# OBCI32_RN42.net
KiCad netlist of a schematic drawn in EAGLE
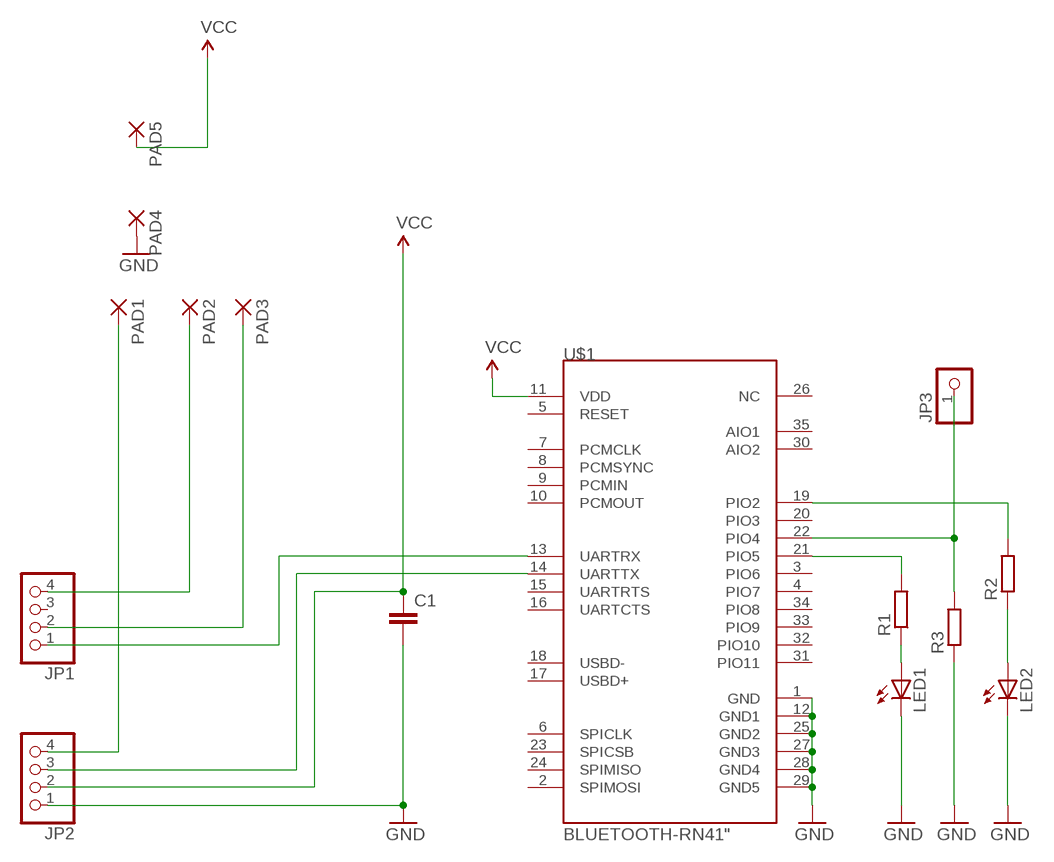
[diagram p0: schematic, sheet 1]

(export (version "E")
  (design (tool "Eeschema 10.0.6"))
  (components
    (comp (ref "C1")
      (value "C-EUC0805")
      (footprint "eagle-import:C0805")
      (libsource (lib "eagle-import") (part "C-EUC0805"))
    )
    (comp (ref "JP1")
      (value "PINHD-1X4")
      (footprint "eagle-import:1X04")
      (libsource (lib "eagle-import") (part "PINHD-1X4"))
    )
    (comp (ref "JP2")
      (value "PINHD-1X4")
      (footprint "eagle-import:1X04")
      (libsource (lib "eagle-import") (part "PINHD-1X4"))
    )
    (comp (ref "JP3")
      (value "PINHD-1X1")
      (footprint "eagle-import:1X01")
      (libsource (lib "eagle-import") (part "PINHD-1X1"))
    )
    (comp (ref "LED1")
      (value "LEDCHIP-LED0805")
      (footprint "eagle-import:CHIP-LED0805")
      (libsource (lib "eagle-import") (part "LEDCHIP-LED0805"))
    )
    (comp (ref "LED2")
      (value "LEDCHIP-LED0805")
      (footprint "eagle-import:CHIP-LED0805")
      (libsource (lib "eagle-import") (part "LEDCHIP-LED0805"))
    )
    (comp (ref "PAD1")
      (value "SMD2")
      (footprint "eagle-import:SMD1,27-2,54")
      (libsource (lib "eagle-import") (part "SMD2"))
    )
    (comp (ref "PAD2")
      (value "SMD2")
      (footprint "eagle-import:SMD1,27-2,54")
      (libsource (lib "eagle-import") (part "SMD2"))
    )
    (comp (ref "PAD3")
      (value "SMD2")
      (footprint "eagle-import:SMD1,27-2,54")
      (libsource (lib "eagle-import") (part "SMD2"))
    )
    (comp (ref "PAD4")
      (value "SMD2")
      (footprint "eagle-import:SMD1,27-2,54")
      (libsource (lib "eagle-import") (part "SMD2"))
    )
    (comp (ref "PAD5")
      (value "SMD2")
      (footprint "eagle-import:SMD1,27-2,54")
      (libsource (lib "eagle-import") (part "SMD2"))
    )
    (comp (ref "R1")
      (value "R-EU_R0603")
      (footprint "eagle-import:R0603")
      (libsource (lib "eagle-import") (part "R-EU_R0603"))
    )
    (comp (ref "R2")
      (value "R-EU_R0603")
      (footprint "eagle-import:R0603")
      (libsource (lib "eagle-import") (part "R-EU_R0603"))
    )
    (comp (ref "R3")
      (value "R-EU_R0603")
      (footprint "eagle-import:R0603")
      (libsource (lib "eagle-import") (part "R-EU_R0603"))
    )
    (comp (ref "U$1")
      (value "BLUETOOTH-RN41\"")
      (footprint "eagle-import:RN41")
      (libsource (lib "eagle-import") (part "BLUETOOTH-RN41{dblquote}"))
    )
  )
  (nets
    (net (code "1") (name "GND") (class "Default")
      (node (ref "C1") (pin "2") (pinfunction "2_2") (pintype "passive"))
      (node (ref "JP2") (pin "1") (pinfunction "1_1") (pintype "passive"))
      (node (ref "LED1") (pin "C") (pinfunction "C_C") (pintype "passive"))
      (node (ref "LED2") (pin "C") (pinfunction "C_C") (pintype "passive"))
      (node (ref "PAD4") (pin "1") (pinfunction "P_1") (pintype "passive"))
      (node (ref "R3") (pin "1") (pinfunction "1_1") (pintype "passive"))
      (node (ref "U$1") (pin "1") (pinfunction "GND_1") (pintype "bidirectional"))
      (node (ref "U$1") (pin "12") (pinfunction "GND1_12") (pintype "bidirectional"))
      (node (ref "U$1") (pin "25") (pinfunction "GND2_25") (pintype "bidirectional"))
      (node (ref "U$1") (pin "27") (pinfunction "GND3_27") (pintype "bidirectional"))
      (node (ref "U$1") (pin "28") (pinfunction "GND4_28") (pintype "bidirectional"))
      (node (ref "U$1") (pin "29") (pinfunction "GND5_29") (pintype "bidirectional"))
    )
    (net (code "2") (name "Net-(LED1-PadA)") (class "Default")
      (node (ref "LED1") (pin "A") (pinfunction "A_A") (pintype "passive"))
      (node (ref "R1") (pin "1") (pinfunction "1_1") (pintype "passive"))
    )
    (net (code "3") (name "Net-(LED2-PadA)") (class "Default")
      (node (ref "LED2") (pin "A") (pinfunction "A_A") (pintype "passive"))
      (node (ref "R2") (pin "1") (pinfunction "1_1") (pintype "passive"))
    )
    (net (code "4") (name "Net-(PAD1-P)") (class "Default")
      (node (ref "JP2") (pin "4") (pinfunction "4_4") (pintype "passive"))
      (node (ref "PAD1") (pin "1") (pinfunction "P_1") (pintype "passive"))
    )
    (net (code "5") (name "Net-(PAD2-P)") (class "Default")
      (node (ref "JP1") (pin "4") (pinfunction "4_4") (pintype "passive"))
      (node (ref "PAD2") (pin "1") (pinfunction "P_1") (pintype "passive"))
    )
    (net (code "6") (name "Net-(PAD3-P)") (class "Default")
      (node (ref "JP1") (pin "2") (pinfunction "2_2") (pintype "passive"))
      (node (ref "PAD3") (pin "1") (pinfunction "P_1") (pintype "passive"))
    )
    (net (code "7") (name "Net-(U$1-PIO2)") (class "Default")
      (node (ref "R2") (pin "2") (pinfunction "2_2") (pintype "passive"))
      (node (ref "U$1") (pin "19") (pinfunction "PIO2_19") (pintype "bidirectional"))
    )
    (net (code "8") (name "Net-(U$1-PIO4)") (class "Default")
      (node (ref "JP3") (pin "1") (pinfunction "1_1") (pintype "passive"))
      (node (ref "R3") (pin "2") (pinfunction "2_2") (pintype "passive"))
      (node (ref "U$1") (pin "22") (pinfunction "PIO4_22") (pintype "bidirectional"))
    )
    (net (code "9") (name "Net-(U$1-PIO5)") (class "Default")
      (node (ref "R1") (pin "2") (pinfunction "2_2") (pintype "passive"))
      (node (ref "U$1") (pin "21") (pinfunction "PIO5_21") (pintype "bidirectional"))
    )
    (net (code "10") (name "Net-(U$1-UARTRX)") (class "Default")
      (node (ref "JP1") (pin "1") (pinfunction "1_1") (pintype "passive"))
      (node (ref "U$1") (pin "13") (pinfunction "UARTRX_13") (pintype "bidirectional"))
    )
    (net (code "11") (name "Net-(U$1-UARTTX)") (class "Default")
      (node (ref "JP2") (pin "3") (pinfunction "3_3") (pintype "passive"))
      (node (ref "U$1") (pin "14") (pinfunction "UARTTX_14") (pintype "bidirectional"))
    )
    (net (code "12") (name "VCC") (class "Default")
      (node (ref "C1") (pin "1") (pinfunction "1_1") (pintype "passive"))
      (node (ref "JP2") (pin "2") (pinfunction "2_2") (pintype "passive"))
      (node (ref "PAD5") (pin "1") (pinfunction "P_1") (pintype "passive"))
      (node (ref "U$1") (pin "11") (pinfunction "VDD_11") (pintype "bidirectional"))
    )
    (net (code "13") (name "unconnected-(JP1-Pad3)") (class "Default")
      (node (ref "JP1") (pin "3") (pinfunction "3_3") (pintype "passive"))
    )
    (net (code "14") (name "unconnected-(U$1-AIO1-Pad35)") (class "Default")
      (node (ref "U$1") (pin "35") (pinfunction "AIO1_35") (pintype "bidirectional"))
    )
    (net (code "15") (name "unconnected-(U$1-AIO2-Pad30)") (class "Default")
      (node (ref "U$1") (pin "30") (pinfunction "AIO2_30") (pintype "bidirectional"))
    )
    (net (code "16") (name "unconnected-(U$1-NC-Pad26)") (class "Default")
      (node (ref "U$1") (pin "26") (pinfunction "NC_26") (pintype "bidirectional"))
    )
    (net (code "17") (name "unconnected-(U$1-PCMCLK-Pad7)") (class "Default")
      (node (ref "U$1") (pin "7") (pinfunction "PCMCLK_7") (pintype "bidirectional"))
    )
    (net (code "18") (name "unconnected-(U$1-PCMIN-Pad9)") (class "Default")
      (node (ref "U$1") (pin "9") (pinfunction "PCMIN_9") (pintype "bidirectional"))
    )
    (net (code "19") (name "unconnected-(U$1-PCMOUT-Pad10)") (class "Default")
      (node (ref "U$1") (pin "10") (pinfunction "PCMOUT_10") (pintype "bidirectional"))
    )
    (net (code "20") (name "unconnected-(U$1-PCMSYNC-Pad8)") (class "Default")
      (node (ref "U$1") (pin "8") (pinfunction "PCMSYNC_8") (pintype "bidirectional"))
    )
    (net (code "21") (name "unconnected-(U$1-PIO3-Pad20)") (class "Default")
      (node (ref "U$1") (pin "20") (pinfunction "PIO3_20") (pintype "bidirectional"))
    )
    (net (code "22") (name "unconnected-(U$1-PIO6-Pad3)") (class "Default")
      (node (ref "U$1") (pin "3") (pinfunction "PIO6_3") (pintype "bidirectional"))
    )
    (net (code "23") (name "unconnected-(U$1-PIO7-Pad4)") (class "Default")
      (node (ref "U$1") (pin "4") (pinfunction "PIO7_4") (pintype "bidirectional"))
    )
    (net (code "24") (name "unconnected-(U$1-PIO8-Pad34)") (class "Default")
      (node (ref "U$1") (pin "34") (pinfunction "PIO8_34") (pintype "bidirectional"))
    )
    (net (code "25") (name "unconnected-(U$1-PIO9-Pad33)") (class "Default")
      (node (ref "U$1") (pin "33") (pinfunction "PIO9_33") (pintype "bidirectional"))
    )
    (net (code "26") (name "unconnected-(U$1-PIO10-Pad32)") (class "Default")
      (node (ref "U$1") (pin "32") (pinfunction "PIO10_32") (pintype "bidirectional"))
    )
    (net (code "27") (name "unconnected-(U$1-PIO11-Pad31)") (class "Default")
      (node (ref "U$1") (pin "31") (pinfunction "PIO11_31") (pintype "bidirectional"))
    )
    (net (code "28") (name "unconnected-(U$1-RESET-Pad5)") (class "Default")
      (node (ref "U$1") (pin "5") (pinfunction "RESET_5") (pintype "bidirectional"))
    )
    (net (code "29") (name "unconnected-(U$1-SPICLK-Pad6)") (class "Default")
      (node (ref "U$1") (pin "6") (pinfunction "SPICLK_6") (pintype "bidirectional"))
    )
    (net (code "30") (name "unconnected-(U$1-SPICSB-Pad23)") (class "Default")
      (node (ref "U$1") (pin "23") (pinfunction "SPICSB_23") (pintype "bidirectional"))
    )
    (net (code "31") (name "unconnected-(U$1-SPIMISO-Pad24)") (class "Default")
      (node (ref "U$1") (pin "24") (pinfunction "SPIMISO_24") (pintype "bidirectional"))
    )
    (net (code "32") (name "unconnected-(U$1-SPIMOSI-Pad2)") (class "Default")
      (node (ref "U$1") (pin "2") (pinfunction "SPIMOSI_2") (pintype "bidirectional"))
    )
    (net (code "33") (name "unconnected-(U$1-UARTCTS-Pad16)") (class "Default")
      (node (ref "U$1") (pin "16") (pinfunction "UARTCTS_16") (pintype "bidirectional"))
    )
    (net (code "34") (name "unconnected-(U$1-UARTRTS-Pad15)") (class "Default")
      (node (ref "U$1") (pin "15") (pinfunction "UARTRTS_15") (pintype "bidirectional"))
    )
    (net (code "35") (name "unconnected-(U$1-USBD+-Pad17)") (class "Default")
      (node (ref "U$1") (pin "17") (pinfunction "USBD+_17") (pintype "bidirectional"))
    )
    (net (code "36") (name "unconnected-(U$1-USBD--Pad18)") (class "Default")
      (node (ref "U$1") (pin "18") (pinfunction "USBD-_18") (pintype "bidirectional"))
    )
  )
)
